# relay_latch_circuit_B.net
KiCad netlist of a schematic drawn in Altium Designer
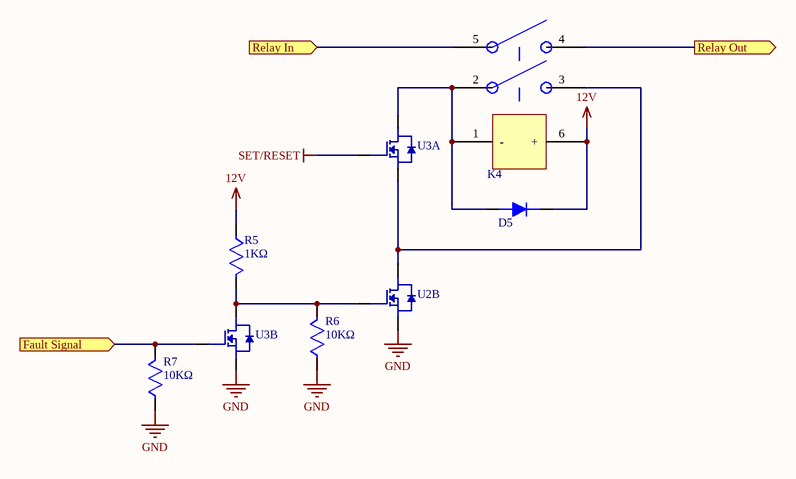
[diagram p0: relay_latch_circuit_B.SchDoc]

(export (version "E")
  (design (tool "Eeschema 10.0.6"))
  (components
    (comp (ref "D5")
      (value "SD560BTR")
      (footprint "DIODE")
      (description "DIODE GEN PURP 600V 5A SMB")
      (fields (field (name "MANUFACTURER") "SMC"))
      (libsource (lib "sdc_prech_schlib") (part "SD560BTR"))
    )
    (comp (ref "K4")
      (value "5-1419124-6")
      (footprint "DPST SDC RELAY")
      (description "General Purpose Relay, Osa Series, Power, Non Latching, Dpst-No, 12 Vdc, 3 A Rohs Compliant: Yes")
      (fields (field (name "MANUFACTURER") "TE Connectivity"))
      (libsource (lib "sdc_prech_schlib") (part "5-1419124-6"))
    )
    (comp (ref "R5")
      (value "1KΩ")
      (footprint "RESISTOR CRCW0603")
      (description "RES SMD 1K OHM 1% 1/10W 0603")
      (fields
        (field (name "MANUFACTURER") "Vishay Dale")
        (field (name "MANUFACTURER PART NUMBER") "CRCW06031K00FKEA")
      )
      (libsource (lib "sdc_prech_schlib") (part "CRCW06031K00FKEA"))
    )
    (comp (ref "R6")
      (value "10KΩ")
      (footprint "RESISTOR CRCW0603")
      (description "RES SMD 10K OHM 1% 1/10W 0603")
      (fields
        (field (name "MANUFACTURER") "Vishay")
        (field (name "MANUFACTURER PART NUMBER") "CRCW060310K0FKEA")
      )
      (libsource (lib "sdc_prech_schlib") (part "CRCW060310K0FKEA"))
    )
    (comp (ref "R7")
      (value "10KΩ")
      (footprint "RESISTOR CRCW0603")
      (description "RES SMD 10K OHM 1% 1/10W 0603")
      (fields
        (field (name "MANUFACTURER") "Vishay")
        (field (name "MANUFACTURER PART NUMBER") "CRCW060310K0FKEA")
      )
      (libsource (lib "sdc_prech_schlib") (part "CRCW060310K0FKEA"))
    )
    (comp (ref "U2")
      (value "SSM6N7002CFU,LF")
      (footprint "N-MOSFET (2 FETS)")
      (description "MOSFET 2N-CH 60V 0.17A US6")
      (fields (field (name "MANUFACTURER") "Toshiba"))
      (libsource (lib "sdc_prech_schlib") (part "SSM6N7002CFU,LF"))
    )
    (comp (ref "U3")
      (value "SSM6N7002CFU,LF")
      (footprint "N-MOSFET (2 FETS)")
      (description "MOSFET 2N-CH 60V 0.17A US6")
      (fields (field (name "MANUFACTURER") "Toshiba"))
      (libsource (lib "sdc_prech_schlib") (part "SSM6N7002CFU,LF"))
    )
  )
  (nets
    (net (code "1") (name "/Fault Signal") (class "Default")
      (node (ref "R7") (pin "2") (pinfunction "2_2") (pintype "passive"))
      (node (ref "U3") (pin "5") (pinfunction "G2_5") (pintype "passive"))
    )
    (net (code "2") (name "/Relay In") (class "Default") (node (ref "K4") (pin "5") (pintype "passive")))
    (net (code "3") (name "/Relay Out") (class "Default") (node (ref "K4") (pin "4") (pintype "passive")))
    (net (code "4") (name "12V") (class "Default")
      (node (ref "D5") (pin "2") (pinfunction "2_2") (pintype "passive"))
      (node (ref "K4") (pin "6") (pinfunction "+_6") (pintype "passive"))
      (node (ref "R5") (pin "1") (pinfunction "1_1") (pintype "passive"))
    )
    (net (code "5") (name "GND") (class "Default")
      (node (ref "R6") (pin "1") (pinfunction "1_1") (pintype "passive"))
      (node (ref "R7") (pin "1") (pinfunction "1_1") (pintype "passive"))
      (node (ref "U2") (pin "4") (pinfunction "S2_4") (pintype "passive"))
      (node (ref "U3") (pin "4") (pinfunction "S2_4") (pintype "passive"))
    )
    (net (code "6") (name "Net-(K4--)") (class "Default")
      (node (ref "D5") (pin "1") (pinfunction "1_1") (pintype "passive"))
      (node (ref "K4") (pin "1") (pinfunction "-_1") (pintype "passive"))
      (node (ref "K4") (pin "2") (pintype "passive"))
      (node (ref "U3") (pin "6") (pinfunction "D1_6") (pintype "passive"))
    )
    (net (code "7") (name "Net-(U2B-D2)") (class "Default")
      (node (ref "K4") (pin "3") (pintype "passive"))
      (node (ref "U2") (pin "3") (pinfunction "D2_3") (pintype "passive"))
      (node (ref "U3") (pin "1") (pinfunction "S1_1") (pintype "passive"))
    )
    (net (code "8") (name "Net-(U2B-G2)") (class "Default")
      (node (ref "R5") (pin "2") (pinfunction "2_2") (pintype "passive"))
      (node (ref "R6") (pin "2") (pinfunction "2_2") (pintype "passive"))
      (node (ref "U2") (pin "5") (pinfunction "G2_5") (pintype "passive"))
      (node (ref "U3") (pin "3") (pinfunction "D2_3") (pintype "passive"))
    )
    (net (code "9") (name "SET{slash}RESET") (class "Default")
      (node (ref "U3") (pin "2") (pinfunction "G1_2") (pintype "passive"))
    )
  )
)
